# PCB_v3.net
KiCad netlist of a schematic drawn in EAGLE
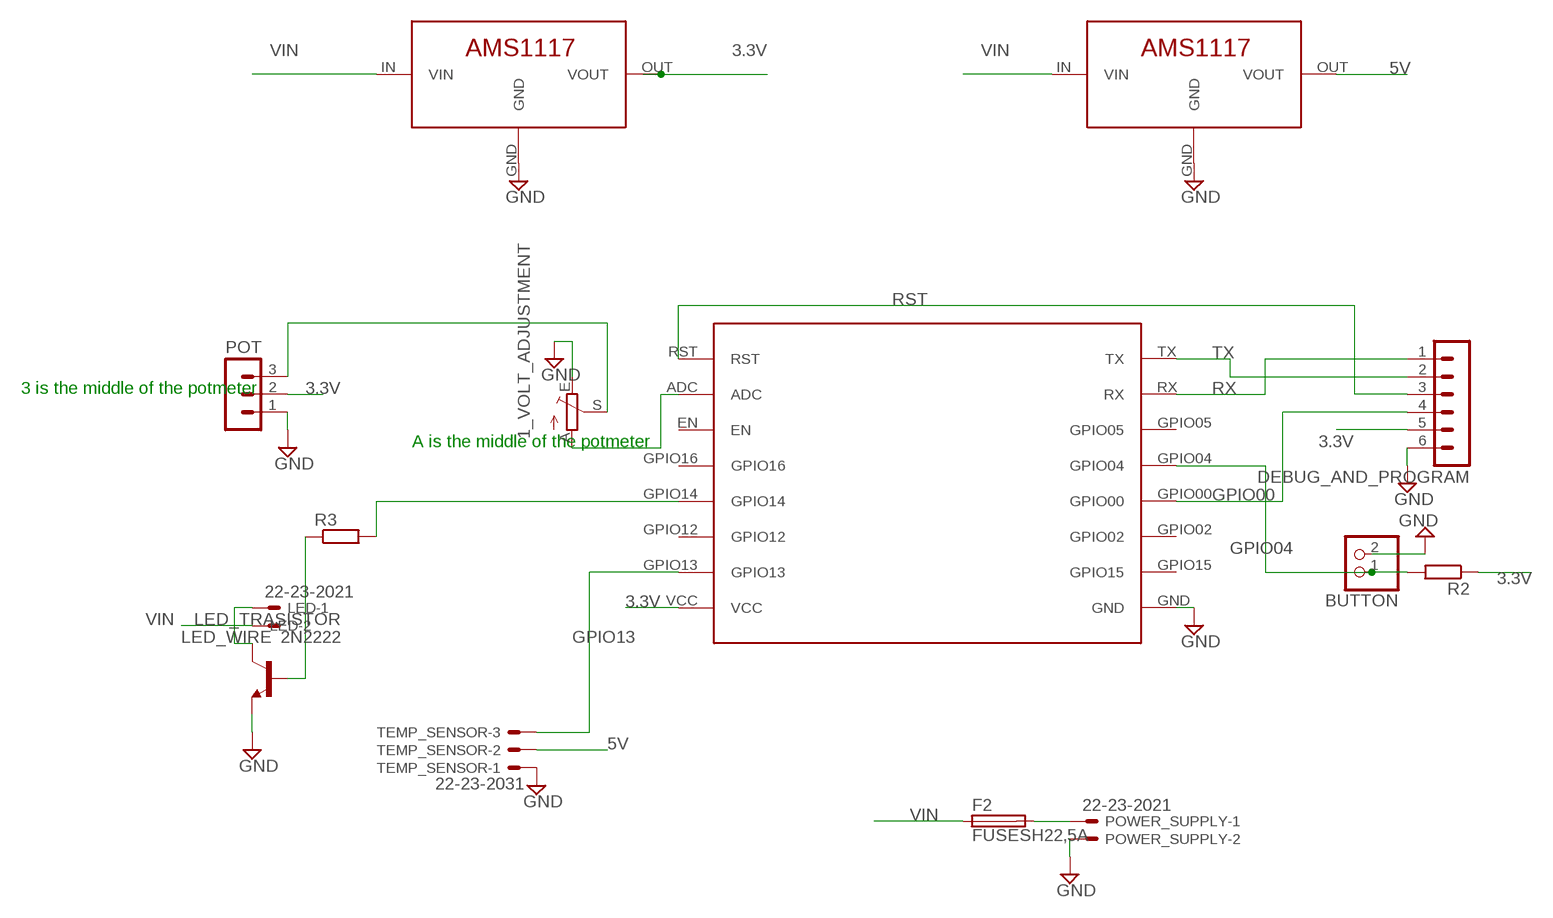
[diagram p0: schematic, sheet 1]

(export (version "E")
  (design (tool "Eeschema 10.0.6"))
  (components
    (comp (ref "1_VOLT_ADJUSTMENT")
      (value "TRIM_EU-CA6V")
      (footprint "eagle-import:CA6V")
      (libsource (lib "eagle-import") (part "TRIM_EU-CA6V"))
    )
    (comp (ref "3.3V_REGULATOR")
      (value "AMS1117")
      (footprint "eagle-import:AMS1117")
      (libsource (lib "eagle-import") (part "AMS1117"))
    )
    (comp (ref "5V_REGULATOR")
      (value "AMS1117")
      (footprint "eagle-import:AMS1117")
      (libsource (lib "eagle-import") (part "AMS1117"))
    )
    (comp (ref "BUTTON")
      (value "PINHD-1X2")
      (footprint "eagle-import:1X02")
      (libsource (lib "eagle-import") (part "PINHD-1X2"))
    )
    (comp (ref "DEBUG_AND_PROGRAM")
      (value "MA06-1")
      (footprint "eagle-import:MA06-1")
      (libsource (lib "eagle-import") (part "MA06-1"))
    )
    (comp (ref "F2")
      (value "FUSESH22,5A")
      (footprint "eagle-import:SH22,5A")
      (libsource (lib "eagle-import") (part "FUSESH22,5A"))
    )
    (comp (ref "LED")
      (value "22-23-2021")
      (footprint "eagle-import:22-23-2021")
      (fields (field (name "MF") "MOLEX"))
      (libsource (lib "eagle-import") (part "22-23-2021"))
    )
    (comp (ref "LED_TRASISTOR")
      (value "2N2222")
      (footprint "eagle-import:2N2222")
      (libsource (lib "eagle-import") (part "2N2222"))
    )
    (comp (ref "POT")
      (value "MA03-1")
      (footprint "eagle-import:MA03-1")
      (libsource (lib "eagle-import") (part "MA03-1"))
    )
    (comp (ref "POWER_SUPPLY")
      (value "22-23-2021")
      (footprint "eagle-import:22-23-2021")
      (fields (field (name "MF") "MOLEX"))
      (libsource (lib "eagle-import") (part "22-23-2021"))
    )
    (comp (ref "R2")
      (value "R-EU_0309/12")
      (footprint "eagle-import:0309_12")
      (libsource (lib "eagle-import") (part "R-EU_0309/12"))
    )
    (comp (ref "R3")
      (value "R-EU_0309/12")
      (footprint "eagle-import:0309_12")
      (libsource (lib "eagle-import") (part "R-EU_0309/12"))
    )
    (comp (ref "TEMP_SENSOR")
      (value "22-23-2031")
      (footprint "eagle-import:22-23-2031")
      (fields (field (name "MF") "MOLEX"))
      (libsource (lib "eagle-import") (part "22-23-2031"))
    )
    (comp (ref "U$1")
      (value "ESP8266")
      (footprint "eagle-import:ESP8266")
      (libsource (lib "eagle-import") (part "ESP8266"))
    )
  )
  (nets
    (net (code "1") (name "/3.3V") (class "Default")
      (node (ref "3.3V_REGULATOR") (pin "OUT") (pinfunction "VOUT_OUT") (pintype "bidirectional"))
      (node (ref "DEBUG_AND_PROGRAM") (pin "5") (pinfunction "5_5") (pintype "passive"))
      (node (ref "POT") (pin "2") (pinfunction "2_2") (pintype "passive"))
      (node (ref "R2") (pin "1") (pinfunction "1_1") (pintype "passive"))
      (node (ref "U$1") (pin "VCC") (pinfunction "VCC_VCC") (pintype "bidirectional"))
    )
    (net (code "2") (name "/5V") (class "Default")
      (node (ref "5V_REGULATOR") (pin "OUT") (pinfunction "VOUT_OUT") (pintype "bidirectional"))
      (node (ref "TEMP_SENSOR") (pin "2") (pinfunction "S_2") (pintype "passive"))
    )
    (net (code "3") (name "/GPIO00") (class "Default")
      (node (ref "DEBUG_AND_PROGRAM") (pin "4") (pinfunction "4_4") (pintype "passive"))
      (node (ref "U$1") (pin "GPIO00") (pinfunction "GPIO00_GPIO00") (pintype "bidirectional"))
    )
    (net (code "4") (name "/GPIO04") (class "Default")
      (node (ref "BUTTON") (pin "1") (pinfunction "1_1") (pintype "passive"))
      (node (ref "R2") (pin "2") (pinfunction "2_2") (pintype "passive"))
      (node (ref "U$1") (pin "GPIO04") (pinfunction "GPIO04_GPIO04") (pintype "bidirectional"))
    )
    (net (code "5") (name "/GPIO13") (class "Default")
      (node (ref "TEMP_SENSOR") (pin "3") (pinfunction "S_3") (pintype "passive"))
      (node (ref "U$1") (pin "GPIO13") (pinfunction "GPIO13_GPIO13") (pintype "bidirectional"))
    )
    (net (code "6") (name "/LED_WIRE") (class "Default")
      (node (ref "LED") (pin "1") (pinfunction "S_1") (pintype "passive"))
      (node (ref "LED_TRASISTOR") (pin "C") (pinfunction "C_C") (pintype "passive"))
    )
    (net (code "7") (name "/RST") (class "Default")
      (node (ref "DEBUG_AND_PROGRAM") (pin "3") (pinfunction "3_3") (pintype "passive"))
      (node (ref "U$1") (pin "RST") (pinfunction "RST_RST") (pintype "bidirectional"))
    )
    (net (code "8") (name "/RX") (class "Default")
      (node (ref "DEBUG_AND_PROGRAM") (pin "1") (pinfunction "1_1") (pintype "passive"))
      (node (ref "U$1") (pin "RX") (pinfunction "RX_RX") (pintype "bidirectional"))
    )
    (net (code "9") (name "/TX") (class "Default")
      (node (ref "DEBUG_AND_PROGRAM") (pin "2") (pinfunction "2_2") (pintype "passive"))
      (node (ref "U$1") (pin "TX") (pinfunction "TX_TX") (pintype "bidirectional"))
    )
    (net (code "10") (name "/VIN") (class "Default")
      (node (ref "3.3V_REGULATOR") (pin "IN") (pinfunction "VIN_IN") (pintype "bidirectional"))
      (node (ref "5V_REGULATOR") (pin "IN") (pinfunction "VIN_IN") (pintype "bidirectional"))
      (node (ref "F2") (pin "1") (pinfunction "1_1") (pintype "passive"))
      (node (ref "LED") (pin "2") (pinfunction "S_2") (pintype "passive"))
    )
    (net (code "11") (name "GND") (class "Default")
      (node (ref "1_VOLT_ADJUSTMENT") (pin "E") (pinfunction "E_E") (pintype "passive"))
      (node (ref "3.3V_REGULATOR") (pin "GND") (pinfunction "GND_GND") (pintype "bidirectional"))
      (node (ref "5V_REGULATOR") (pin "GND") (pinfunction "GND_GND") (pintype "bidirectional"))
      (node (ref "BUTTON") (pin "2") (pinfunction "2_2") (pintype "passive"))
      (node (ref "DEBUG_AND_PROGRAM") (pin "6") (pinfunction "6_6") (pintype "passive"))
      (node (ref "LED_TRASISTOR") (pin "E") (pinfunction "E_E") (pintype "passive"))
      (node (ref "POT") (pin "1") (pinfunction "1_1") (pintype "passive"))
      (node (ref "POWER_SUPPLY") (pin "2") (pinfunction "S_2") (pintype "passive"))
      (node (ref "TEMP_SENSOR") (pin "1") (pinfunction "S_1") (pintype "passive"))
      (node (ref "U$1") (pin "GND") (pinfunction "GND_GND") (pintype "bidirectional"))
    )
    (net (code "12") (name "Net-(1_VOLT_ADJUSTMENT-PadA)") (class "Default")
      (node (ref "1_VOLT_ADJUSTMENT") (pin "A") (pinfunction "A_A") (pintype "passive"))
      (node (ref "U$1") (pin "ADC") (pinfunction "ADC_ADC") (pintype "bidirectional"))
    )
    (net (code "13") (name "Net-(1_VOLT_ADJUSTMENT-PadS)") (class "Default")
      (node (ref "1_VOLT_ADJUSTMENT") (pin "S") (pinfunction "S_S") (pintype "passive"))
      (node (ref "POT") (pin "3") (pinfunction "3_3") (pintype "passive"))
    )
    (net (code "14") (name "Net-(LED_TRASISTOR-PadB)") (class "Default")
      (node (ref "LED_TRASISTOR") (pin "B") (pinfunction "B_B") (pintype "passive"))
      (node (ref "R3") (pin "1") (pinfunction "1_1") (pintype "passive"))
    )
    (net (code "15") (name "Net-(POWER_SUPPLYA-S)") (class "Default")
      (node (ref "F2") (pin "2") (pinfunction "2_2") (pintype "passive"))
      (node (ref "POWER_SUPPLY") (pin "1") (pinfunction "S_1") (pintype "passive"))
    )
    (net (code "16") (name "Net-(R3-Pad2)") (class "Default")
      (node (ref "R3") (pin "2") (pinfunction "2_2") (pintype "passive"))
      (node (ref "U$1") (pin "GPIO14") (pinfunction "GPIO14_GPIO14") (pintype "bidirectional"))
    )
    (net (code "17") (name "unconnected-(U$1-PadEN)") (class "Default")
      (node (ref "U$1") (pin "EN") (pinfunction "EN_EN") (pintype "bidirectional"))
    )
    (net (code "18") (name "unconnected-(U$1-PadGPIO02)") (class "Default")
      (node (ref "U$1") (pin "GPIO02") (pinfunction "GPIO02_GPIO02") (pintype "bidirectional"))
    )
    (net (code "19") (name "unconnected-(U$1-PadGPIO05)") (class "Default")
      (node (ref "U$1") (pin "GPIO05") (pinfunction "GPIO05_GPIO05") (pintype "bidirectional"))
    )
    (net (code "20") (name "unconnected-(U$1-PadGPIO12)") (class "Default")
      (node (ref "U$1") (pin "GPIO12") (pinfunction "GPIO12_GPIO12") (pintype "bidirectional"))
    )
    (net (code "21") (name "unconnected-(U$1-PadGPIO15)") (class "Default")
      (node (ref "U$1") (pin "GPIO15") (pinfunction "GPIO15_GPIO15") (pintype "bidirectional"))
    )
    (net (code "22") (name "unconnected-(U$1-PadGPIO16)") (class "Default")
      (node (ref "U$1") (pin "GPIO16") (pinfunction "GPIO16_GPIO16") (pintype "bidirectional"))
    )
  )
)
